# MAINBOARD.net
KiCad netlist of a schematic drawn in EasyEDA Pro
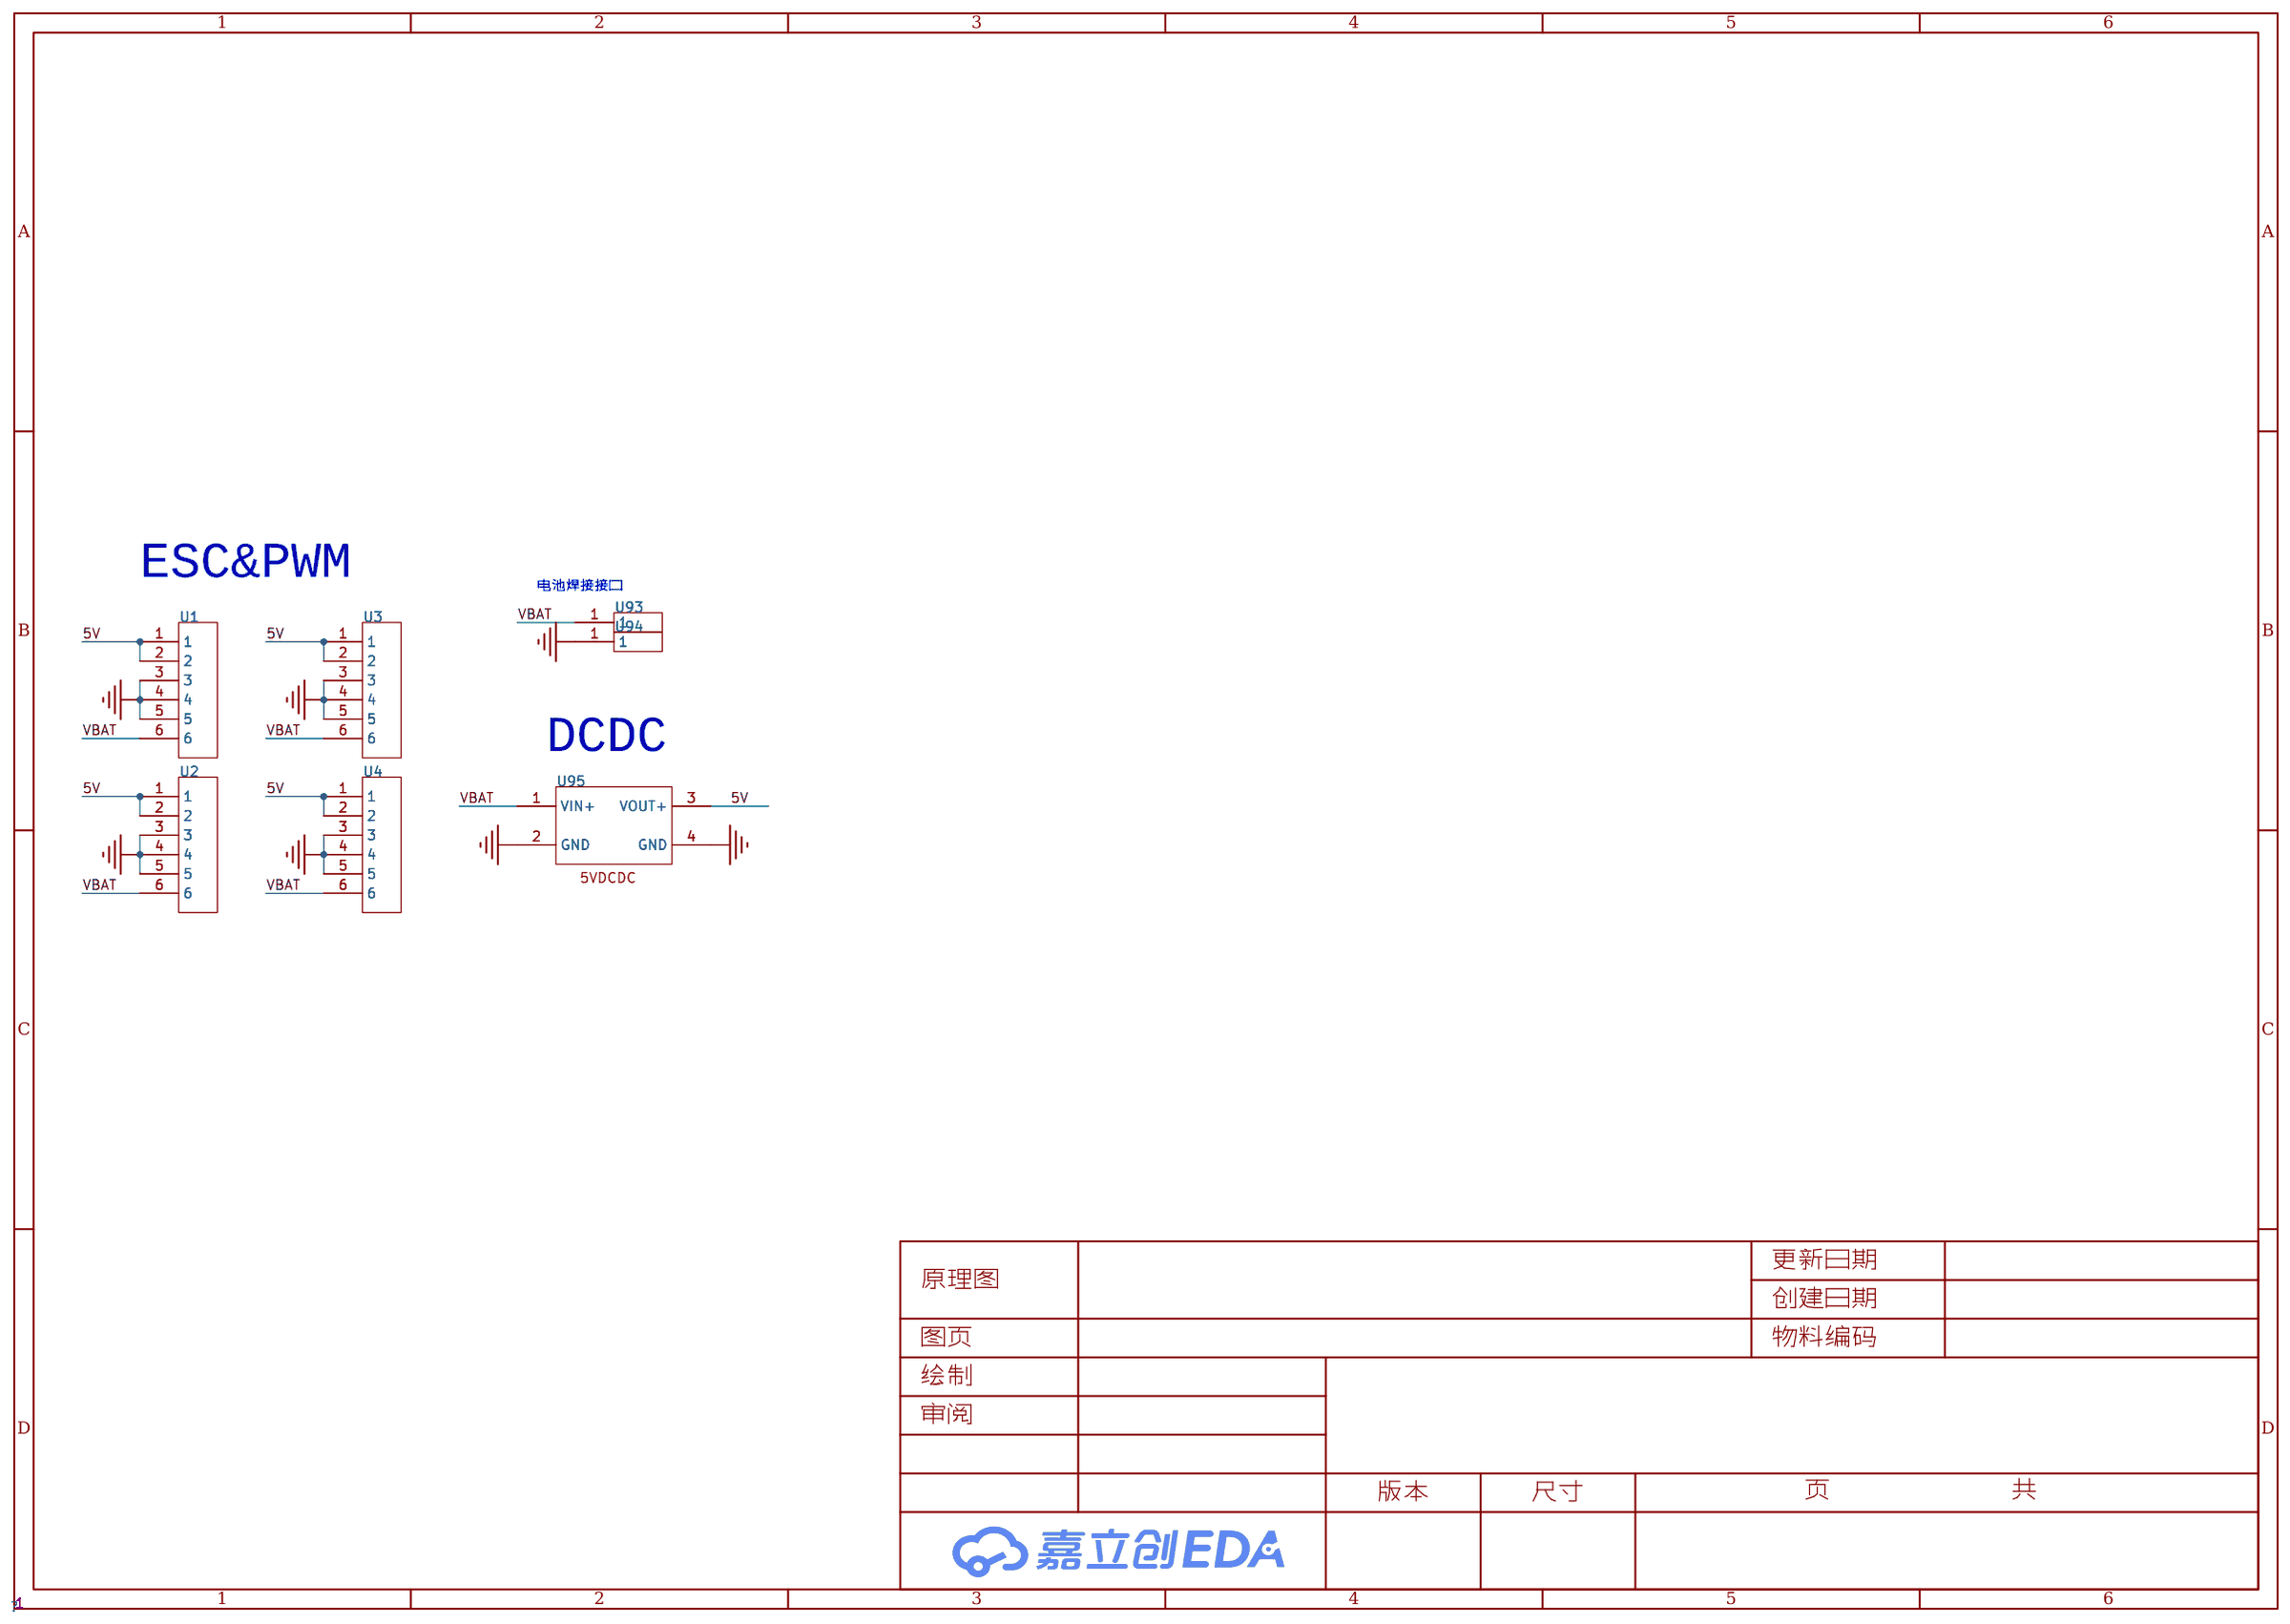
[diagram p0: schematic sheet]

(export (version "E")
  (design (tool "Eeschema 10.0.6"))
  (components
    (comp (ref "U1")
      (value "~")
      (footprint "easyedapro:6pin焊接引出")
      (libsource (lib "easyedapro") (part "6pin焊接引出"))
    )
    (comp (ref "U2")
      (value "~")
      (footprint "easyedapro:6pin焊接引出")
      (libsource (lib "easyedapro") (part "6pin焊接引出"))
    )
    (comp (ref "U3")
      (value "~")
      (footprint "easyedapro:6pin焊接引出")
      (libsource (lib "easyedapro") (part "6pin焊接引出"))
    )
    (comp (ref "U4")
      (value "~")
      (footprint "easyedapro:6pin焊接引出")
      (libsource (lib "easyedapro") (part "6pin焊接引出"))
    )
    (comp (ref "U93") (value "~") (footprint "easyedapro:表面焊盘") (libsource (lib "easyedapro") (part "表面焊盘")))
    (comp (ref "U94") (value "~") (footprint "easyedapro:表面焊盘") (libsource (lib "easyedapro") (part "表面焊盘")))
    (comp (ref "U95")
      (value "~")
      (description "蓝色DCDC降压模块（贴片）")
      (libsource (lib "easyedapro") (part "DCDC-5V"))
    )
  )
  (nets
    (net (code "1") (name "/5V") (class "Default")
      (node (ref "U1") (pin "1") (pinfunction "1_1") (pintype "input"))
      (node (ref "U1") (pin "2") (pinfunction "2_2") (pintype "input"))
      (node (ref "U2") (pin "1") (pinfunction "1_1") (pintype "input"))
      (node (ref "U2") (pin "2") (pinfunction "2_2") (pintype "input"))
      (node (ref "U3") (pin "1") (pinfunction "1_1") (pintype "input"))
      (node (ref "U3") (pin "2") (pinfunction "2_2") (pintype "input"))
      (node (ref "U4") (pin "1") (pinfunction "1_1") (pintype "input"))
      (node (ref "U4") (pin "2") (pinfunction "2_2") (pintype "input"))
      (node (ref "U95") (pin "3") (pinfunction "VOUT+_3") (pintype "input"))
    )
    (net (code "2") (name "/VBAT") (class "Default")
      (node (ref "U1") (pin "6") (pinfunction "6_6") (pintype "input"))
      (node (ref "U2") (pin "6") (pinfunction "6_6") (pintype "input"))
      (node (ref "U3") (pin "6") (pinfunction "6_6") (pintype "input"))
      (node (ref "U4") (pin "6") (pinfunction "6_6") (pintype "input"))
      (node (ref "U93") (pin "1") (pinfunction "1_1") (pintype "input"))
      (node (ref "U95") (pin "1") (pinfunction "VIN+_1") (pintype "input"))
    )
    (net (code "3") (name "GND") (class "Default")
      (node (ref "U1") (pin "3") (pinfunction "3_3") (pintype "input"))
      (node (ref "U1") (pin "4") (pinfunction "4_4") (pintype "input"))
      (node (ref "U1") (pin "5") (pinfunction "5_5") (pintype "input"))
      (node (ref "U2") (pin "3") (pinfunction "3_3") (pintype "input"))
      (node (ref "U2") (pin "4") (pinfunction "4_4") (pintype "input"))
      (node (ref "U2") (pin "5") (pinfunction "5_5") (pintype "input"))
      (node (ref "U3") (pin "3") (pinfunction "3_3") (pintype "input"))
      (node (ref "U3") (pin "4") (pinfunction "4_4") (pintype "input"))
      (node (ref "U3") (pin "5") (pinfunction "5_5") (pintype "input"))
      (node (ref "U4") (pin "3") (pinfunction "3_3") (pintype "input"))
      (node (ref "U4") (pin "4") (pinfunction "4_4") (pintype "input"))
      (node (ref "U4") (pin "5") (pinfunction "5_5") (pintype "input"))
      (node (ref "U94") (pin "1") (pinfunction "1_1") (pintype "input"))
      (node (ref "U95") (pin "2") (pinfunction "GND_2") (pintype "input"))
      (node (ref "U95") (pin "4") (pinfunction "GND_4") (pintype "input"))
    )
  )
)
